# I2C2_6_0.net
KiCad netlist of a schematic drawn in EAGLE
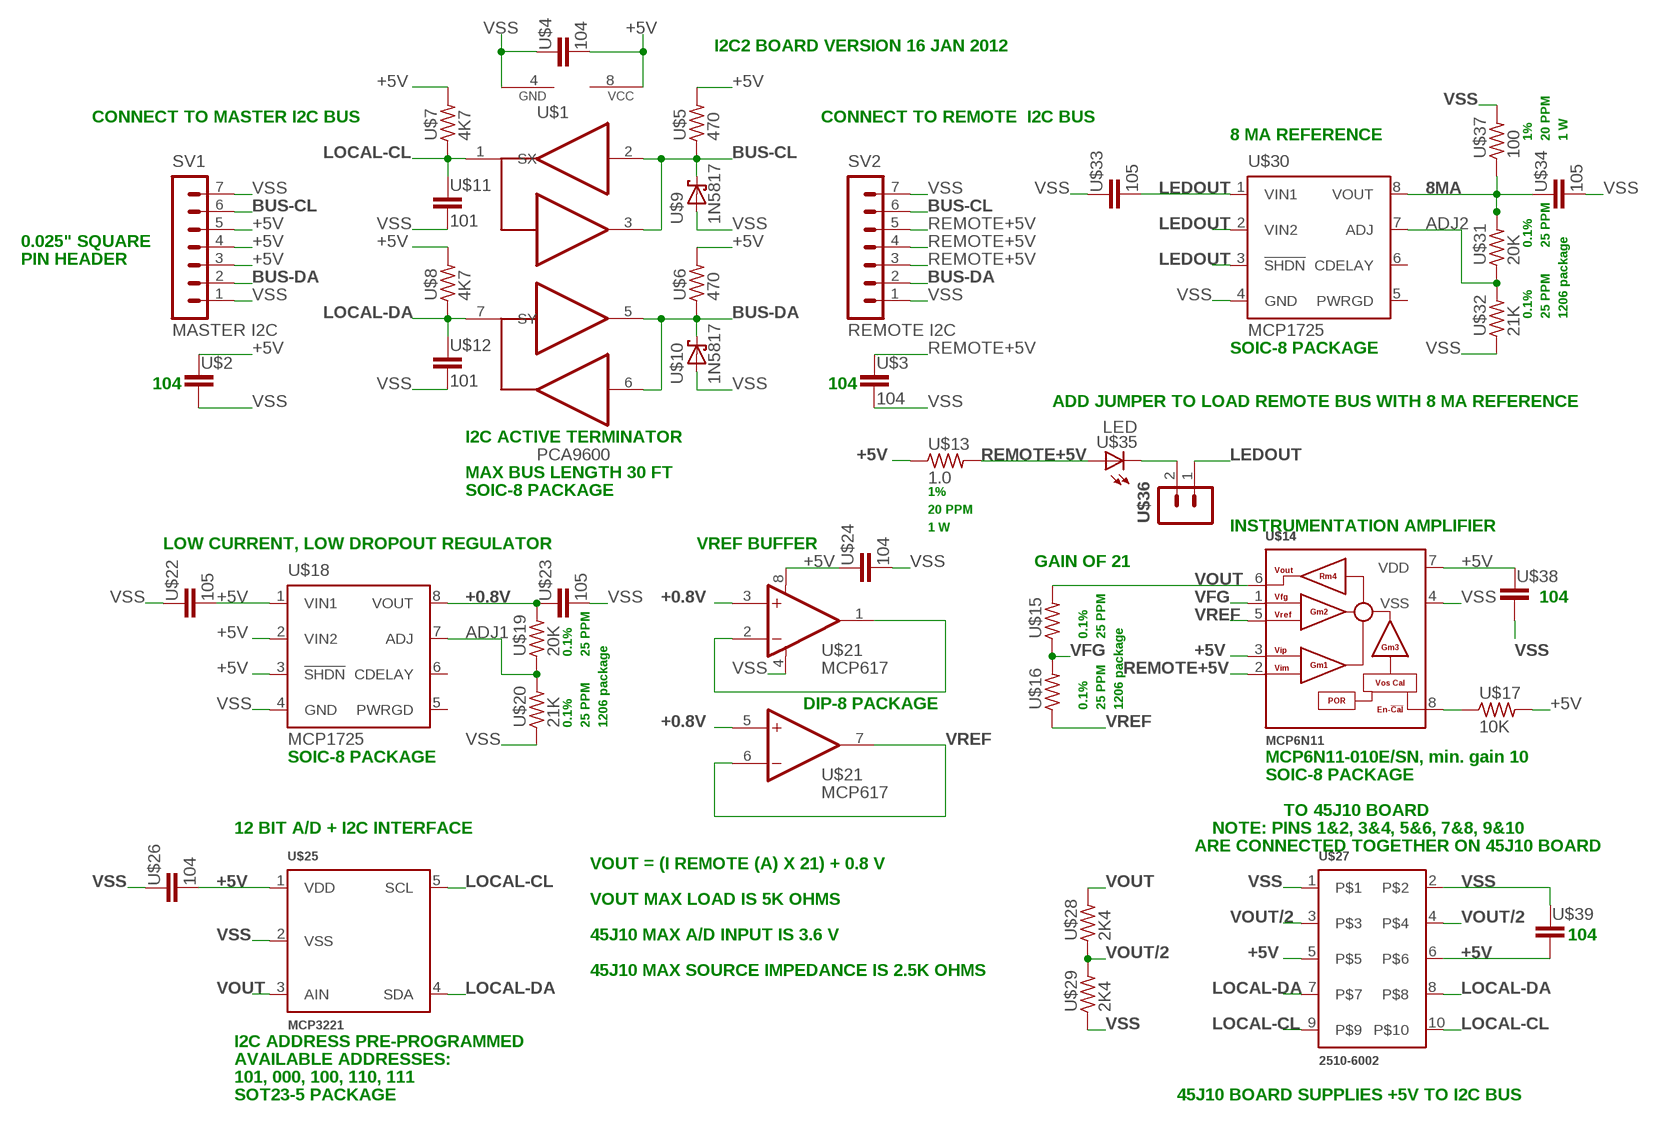
[diagram p0: schematic, sheet 1]

(export (version "E")
  (design (tool "Eeschema 10.0.6"))
  (components
    (comp (ref "SV1")
      (value "MASTER I2C")
      (footprint "eagle-import:MA07-1")
      (libsource (lib "eagle-import") (part "MA07-1"))
    )
    (comp (ref "SV2")
      (value "REMOTE I2C")
      (footprint "eagle-import:MA07-1")
      (libsource (lib "eagle-import") (part "MA07-1"))
    )
    (comp (ref "U$1")
      (value "PCA9600")
      (footprint "eagle-import:SO08")
      (libsource (lib "eagle-import") (part "PCA9600SO8"))
    )
    (comp (ref "U$2")
      (value "C2.5-5")
      (footprint "eagle-import:C2.5-5")
      (libsource (lib "eagle-import") (part "C2.5-5"))
    )
    (comp (ref "U$3")
      (value "104")
      (footprint "eagle-import:C2.5-5")
      (libsource (lib "eagle-import") (part "C2.5-5"))
    )
    (comp (ref "U$4")
      (value "104")
      (footprint "eagle-import:C2.5-5")
      (libsource (lib "eagle-import") (part "C2.5-5"))
    )
    (comp (ref "U$5")
      (value "470")
      (footprint "eagle-import:R-1_4W")
      (libsource (lib "eagle-import") (part "R-1/4W"))
    )
    (comp (ref "U$6")
      (value "470")
      (footprint "eagle-import:R-1_4W")
      (libsource (lib "eagle-import") (part "R-1/4W"))
    )
    (comp (ref "U$7")
      (value "4K7")
      (footprint "eagle-import:R-1_4W")
      (libsource (lib "eagle-import") (part "R-1/4W"))
    )
    (comp (ref "U$8")
      (value "4K7")
      (footprint "eagle-import:R-1_4W")
      (libsource (lib "eagle-import") (part "R-1/4W"))
    )
    (comp (ref "U$9")
      (value "1N5817")
      (footprint "eagle-import:1N5817")
      (libsource (lib "eagle-import") (part "1N5817P"))
    )
    (comp (ref "U$10")
      (value "1N5817")
      (footprint "eagle-import:1N5817")
      (libsource (lib "eagle-import") (part "1N5817P"))
    )
    (comp (ref "U$11")
      (value "101")
      (footprint "eagle-import:C2.5-5")
      (libsource (lib "eagle-import") (part "C2.5-5"))
    )
    (comp (ref "U$12")
      (value "101")
      (footprint "eagle-import:C2.5-5")
      (libsource (lib "eagle-import") (part "C2.5-5"))
    )
    (comp (ref "U$13")
      (value "1.0")
      (footprint "eagle-import:R-1W")
      (libsource (lib "eagle-import") (part "R-1W-20PPM"))
    )
    (comp (ref "U$14")
      (value "MCP6N11")
      (footprint "eagle-import:SO08")
      (libsource (lib "eagle-import") (part "MCP6N11-SO08"))
    )
    (comp (ref "U$15")
      (value "R1206")
      (footprint "eagle-import:R1206")
      (libsource (lib "eagle-import") (part "R1206"))
    )
    (comp (ref "U$16")
      (value "R1206")
      (footprint "eagle-import:R1206")
      (libsource (lib "eagle-import") (part "R1206"))
    )
    (comp (ref "U$17")
      (value "10K")
      (footprint "eagle-import:R-1_4W")
      (libsource (lib "eagle-import") (part "R-1/4W"))
    )
    (comp (ref "U$18")
      (value "MCP1725")
      (footprint "eagle-import:SO08")
      (libsource (lib "eagle-import") (part "MCP1725-ADJ"))
    )
    (comp (ref "U$19")
      (value "20K")
      (footprint "eagle-import:R1206")
      (libsource (lib "eagle-import") (part "R1206"))
    )
    (comp (ref "U$20")
      (value "21K")
      (footprint "eagle-import:R1206")
      (libsource (lib "eagle-import") (part "R1206"))
    )
    (comp (ref "U$21")
      (value "MCP617")
      (footprint "eagle-import:DIL08")
      (libsource (lib "eagle-import") (part "MCP617-I/P"))
    )
    (comp (ref "U$22")
      (value "105")
      (footprint "eagle-import:C2.5-5")
      (libsource (lib "eagle-import") (part "C2.5-5"))
    )
    (comp (ref "U$23")
      (value "105")
      (footprint "eagle-import:C2.5-5")
      (libsource (lib "eagle-import") (part "C2.5-5"))
    )
    (comp (ref "U$24")
      (value "104")
      (footprint "eagle-import:C2.5-5")
      (libsource (lib "eagle-import") (part "C2.5-5"))
    )
    (comp (ref "U$25")
      (value "MCP3221")
      (footprint "eagle-import:SOT23-5")
      (libsource (lib "eagle-import") (part "MCP3221"))
    )
    (comp (ref "U$26")
      (value "104")
      (footprint "eagle-import:C2.5-5")
      (libsource (lib "eagle-import") (part "C2.5-5"))
    )
    (comp (ref "U$27")
      (value "2510-6002")
      (footprint "eagle-import:2510-6002")
      (libsource (lib "eagle-import") (part "2510-6002"))
    )
    (comp (ref "U$28")
      (value "2K4")
      (footprint "eagle-import:R-1_4W")
      (libsource (lib "eagle-import") (part "R-1/4W"))
    )
    (comp (ref "U$29")
      (value "2K4")
      (footprint "eagle-import:R-1_4W")
      (libsource (lib "eagle-import") (part "R-1/4W"))
    )
    (comp (ref "U$30")
      (value "MCP1725")
      (footprint "eagle-import:SO08")
      (libsource (lib "eagle-import") (part "MCP1725-ADJ"))
    )
    (comp (ref "U$31")
      (value "20K")
      (footprint "eagle-import:R1206")
      (libsource (lib "eagle-import") (part "R1206"))
    )
    (comp (ref "U$32")
      (value "21K")
      (footprint "eagle-import:R1206")
      (libsource (lib "eagle-import") (part "R1206"))
    )
    (comp (ref "U$33")
      (value "105")
      (footprint "eagle-import:C2.5-5")
      (libsource (lib "eagle-import") (part "C2.5-5"))
    )
    (comp (ref "U$34")
      (value "105")
      (footprint "eagle-import:C2.5-5")
      (libsource (lib "eagle-import") (part "C2.5-5"))
    )
    (comp (ref "U$35")
      (value "LED")
      (footprint "eagle-import:LED1206")
      (libsource (lib "eagle-import") (part "LED-SMD-1206"))
    )
    (comp (ref "U$36")
      (value "MA02-1")
      (footprint "eagle-import:MA02-1")
      (libsource (lib "eagle-import") (part "MA02-1"))
    )
    (comp (ref "U$37")
      (value "100")
      (footprint "eagle-import:R-1W")
      (libsource (lib "eagle-import") (part "R-1W-20PPM"))
    )
    (comp (ref "U$38")
      (value "C2.5-5")
      (footprint "eagle-import:C2.5-5")
      (libsource (lib "eagle-import") (part "C2.5-5"))
    )
    (comp (ref "U$39")
      (value "C2.5-5")
      (footprint "eagle-import:C2.5-5")
      (libsource (lib "eagle-import") (part "C2.5-5"))
    )
  )
  (nets
    (net (code "1") (name "/+0.8V") (class "Default")
      (node (ref "U$18") (pin "8") (pinfunction "VOUT_8") (pintype "power_in"))
      (node (ref "U$19") (pin "2") (pinfunction "2_2") (pintype "passive"))
      (node (ref "U$21") (pin "3") (pinfunction "+IN_3") (pintype "input"))
      (node (ref "U$21") (pin "5") (pinfunction "+IN1_5") (pintype "input"))
      (node (ref "U$23") (pin "1") (pinfunction "1_1") (pintype "passive"))
    )
    (net (code "2") (name "/+5V") (class "Default")
      (node (ref "SV1") (pin "3") (pinfunction "3_3") (pintype "passive"))
      (node (ref "SV1") (pin "4") (pinfunction "4_4") (pintype "passive"))
      (node (ref "SV1") (pin "5") (pinfunction "5_5") (pintype "passive"))
      (node (ref "U$1") (pin "8") (pinfunction "VCC_8") (pintype "power_in"))
      (node (ref "U$13") (pin "1") (pinfunction "1_1") (pintype "passive"))
      (node (ref "U$14") (pin "3") (pinfunction "VIP_3") (pintype "input"))
      (node (ref "U$14") (pin "7") (pinfunction "VDD_7") (pintype "power_in"))
      (node (ref "U$17") (pin "2") (pinfunction "2_2") (pintype "passive"))
      (node (ref "U$18") (pin "1") (pinfunction "VIN1_1") (pintype "power_in"))
      (node (ref "U$18") (pin "2") (pinfunction "VIN2_2") (pintype "power_in"))
      (node (ref "U$18") (pin "3") (pinfunction "~{SHDN}_3") (pintype "input"))
      (node (ref "U$2") (pin "1") (pinfunction "1_1") (pintype "passive"))
      (node (ref "U$21") (pin "8") (pinfunction "V+_8") (pintype "power_in"))
      (node (ref "U$22") (pin "2") (pinfunction "2_2") (pintype "passive"))
      (node (ref "U$24") (pin "1") (pinfunction "1_1") (pintype "passive"))
      (node (ref "U$25") (pin "1") (pinfunction "VDD_1") (pintype "power_in"))
      (node (ref "U$26") (pin "2") (pinfunction "2_2") (pintype "passive"))
      (node (ref "U$27") (pin "5") (pinfunction "P$5_5") (pintype "passive"))
      (node (ref "U$27") (pin "6") (pinfunction "P$6_6") (pintype "passive"))
      (node (ref "U$38") (pin "1") (pinfunction "1_1") (pintype "passive"))
      (node (ref "U$39") (pin "2") (pinfunction "2_2") (pintype "passive"))
      (node (ref "U$4") (pin "2") (pinfunction "2_2") (pintype "passive"))
      (node (ref "U$5") (pin "2") (pinfunction "2_2") (pintype "passive"))
      (node (ref "U$6") (pin "2") (pinfunction "2_2") (pintype "passive"))
      (node (ref "U$7") (pin "2") (pinfunction "2_2") (pintype "passive"))
      (node (ref "U$8") (pin "2") (pinfunction "2_2") (pintype "passive"))
    )
    (net (code "3") (name "/8MA") (class "Default")
      (node (ref "U$30") (pin "8") (pinfunction "VOUT_8") (pintype "power_in"))
      (node (ref "U$31") (pin "2") (pinfunction "2_2") (pintype "passive"))
      (node (ref "U$34") (pin "1") (pinfunction "1_1") (pintype "passive"))
      (node (ref "U$37") (pin "1") (pinfunction "1_1") (pintype "passive"))
    )
    (net (code "4") (name "/ADJ1") (class "Default")
      (node (ref "U$18") (pin "7") (pinfunction "ADJ_7") (pintype "input"))
      (node (ref "U$19") (pin "1") (pinfunction "1_1") (pintype "passive"))
      (node (ref "U$20") (pin "2") (pinfunction "2_2") (pintype "passive"))
    )
    (net (code "5") (name "/ADJ2") (class "Default")
      (node (ref "U$30") (pin "7") (pinfunction "ADJ_7") (pintype "input"))
      (node (ref "U$31") (pin "1") (pinfunction "1_1") (pintype "passive"))
      (node (ref "U$32") (pin "2") (pinfunction "2_2") (pintype "passive"))
    )
    (net (code "6") (name "/BUS-CL") (class "Default")
      (node (ref "SV1") (pin "6") (pinfunction "6_6") (pintype "passive"))
      (node (ref "SV2") (pin "6") (pinfunction "6_6") (pintype "passive"))
      (node (ref "U$1") (pin "2") (pinfunction "RX_2") (pintype "input"))
      (node (ref "U$1") (pin "3") (pinfunction "TX_3") (pintype "output"))
      (node (ref "U$5") (pin "1") (pinfunction "1_1") (pintype "passive"))
      (node (ref "U$9") (pin "C") (pinfunction "C_C") (pintype "passive"))
    )
    (net (code "7") (name "/BUS-DA") (class "Default")
      (node (ref "SV1") (pin "2") (pinfunction "2_2") (pintype "passive"))
      (node (ref "SV2") (pin "2") (pinfunction "2_2") (pintype "passive"))
      (node (ref "U$1") (pin "5") (pinfunction "TY_5") (pintype "output"))
      (node (ref "U$1") (pin "6") (pinfunction "RY_6") (pintype "input"))
      (node (ref "U$10") (pin "C") (pinfunction "C_C") (pintype "passive"))
      (node (ref "U$6") (pin "1") (pinfunction "1_1") (pintype "passive"))
    )
    (net (code "8") (name "/LEDOUT") (class "Default")
      (node (ref "U$30") (pin "1") (pinfunction "VIN1_1") (pintype "power_in"))
      (node (ref "U$30") (pin "2") (pinfunction "VIN2_2") (pintype "power_in"))
      (node (ref "U$30") (pin "3") (pinfunction "~{SHDN}_3") (pintype "input"))
      (node (ref "U$33") (pin "2") (pinfunction "2_2") (pintype "passive"))
      (node (ref "U$36") (pin "1") (pinfunction "1_1") (pintype "passive"))
    )
    (net (code "9") (name "/LOCAL-CL") (class "Default")
      (node (ref "U$1") (pin "1") (pinfunction "SX_1") (pintype "bidirectional"))
      (node (ref "U$11") (pin "1") (pinfunction "1_1") (pintype "passive"))
      (node (ref "U$25") (pin "5") (pinfunction "SCL_5") (pintype "bidirectional"))
      (node (ref "U$27") (pin "10") (pinfunction "P$10_10") (pintype "passive"))
      (node (ref "U$27") (pin "9") (pinfunction "P$9_9") (pintype "passive"))
      (node (ref "U$7") (pin "1") (pinfunction "1_1") (pintype "passive"))
    )
    (net (code "10") (name "/LOCAL-DA") (class "Default")
      (node (ref "U$1") (pin "7") (pinfunction "SY_7") (pintype "bidirectional"))
      (node (ref "U$12") (pin "1") (pinfunction "1_1") (pintype "passive"))
      (node (ref "U$25") (pin "4") (pinfunction "SDA_4") (pintype "bidirectional"))
      (node (ref "U$27") (pin "7") (pinfunction "P$7_7") (pintype "passive"))
      (node (ref "U$27") (pin "8") (pinfunction "P$8_8") (pintype "passive"))
      (node (ref "U$8") (pin "1") (pinfunction "1_1") (pintype "passive"))
    )
    (net (code "11") (name "/REMOTE+5V") (class "Default")
      (node (ref "SV2") (pin "3") (pinfunction "3_3") (pintype "passive"))
      (node (ref "SV2") (pin "4") (pinfunction "4_4") (pintype "passive"))
      (node (ref "SV2") (pin "5") (pinfunction "5_5") (pintype "passive"))
      (node (ref "U$13") (pin "2") (pinfunction "2_2") (pintype "passive"))
      (node (ref "U$14") (pin "2") (pinfunction "VIM_2") (pintype "input"))
      (node (ref "U$3") (pin "1") (pinfunction "1_1") (pintype "passive"))
      (node (ref "U$35") (pin "A") (pinfunction "A_A") (pintype "passive"))
    )
    (net (code "12") (name "/VFG") (class "Default")
      (node (ref "U$14") (pin "1") (pinfunction "VFG_1") (pintype "input"))
      (node (ref "U$15") (pin "1") (pinfunction "1_1") (pintype "passive"))
      (node (ref "U$16") (pin "2") (pinfunction "2_2") (pintype "passive"))
    )
    (net (code "13") (name "/VOUT") (class "Default")
      (node (ref "U$14") (pin "6") (pinfunction "VOUT_6") (pintype "output"))
      (node (ref "U$15") (pin "2") (pinfunction "2_2") (pintype "passive"))
      (node (ref "U$25") (pin "3") (pinfunction "AIN_3") (pintype "input"))
      (node (ref "U$28") (pin "2") (pinfunction "2_2") (pintype "passive"))
    )
    (net (code "14") (name "/VOUT{slash}2") (class "Default")
      (node (ref "U$27") (pin "3") (pinfunction "P$3_3") (pintype "passive"))
      (node (ref "U$27") (pin "4") (pinfunction "P$4_4") (pintype "passive"))
      (node (ref "U$28") (pin "1") (pinfunction "1_1") (pintype "passive"))
      (node (ref "U$29") (pin "2") (pinfunction "2_2") (pintype "passive"))
    )
    (net (code "15") (name "/VREF") (class "Default")
      (node (ref "U$14") (pin "5") (pinfunction "VREF_5") (pintype "input"))
      (node (ref "U$16") (pin "1") (pinfunction "1_1") (pintype "passive"))
      (node (ref "U$21") (pin "6") (pinfunction "-IN1_6") (pintype "input"))
      (node (ref "U$21") (pin "7") (pinfunction "OUT1_7") (pintype "output"))
    )
    (net (code "16") (name "/VSS") (class "Default")
      (node (ref "SV1") (pin "1") (pinfunction "1_1") (pintype "passive"))
      (node (ref "SV1") (pin "7") (pinfunction "7_7") (pintype "passive"))
      (node (ref "SV2") (pin "1") (pinfunction "1_1") (pintype "passive"))
      (node (ref "SV2") (pin "7") (pinfunction "7_7") (pintype "passive"))
      (node (ref "U$1") (pin "4") (pinfunction "GND_4") (pintype "power_in"))
      (node (ref "U$10") (pin "A") (pinfunction "A_A") (pintype "passive"))
      (node (ref "U$11") (pin "2") (pinfunction "2_2") (pintype "passive"))
      (node (ref "U$12") (pin "2") (pinfunction "2_2") (pintype "passive"))
      (node (ref "U$14") (pin "4") (pinfunction "VSS_4") (pintype "power_in"))
      (node (ref "U$18") (pin "4") (pinfunction "GND_4") (pintype "power_in"))
      (node (ref "U$2") (pin "2") (pinfunction "2_2") (pintype "passive"))
      (node (ref "U$20") (pin "1") (pinfunction "1_1") (pintype "passive"))
      (node (ref "U$21") (pin "4") (pinfunction "V-_4") (pintype "power_in"))
      (node (ref "U$22") (pin "1") (pinfunction "1_1") (pintype "passive"))
      (node (ref "U$23") (pin "2") (pinfunction "2_2") (pintype "passive"))
      (node (ref "U$24") (pin "2") (pinfunction "2_2") (pintype "passive"))
      (node (ref "U$25") (pin "2") (pinfunction "VSS_2") (pintype "power_in"))
      (node (ref "U$26") (pin "1") (pinfunction "1_1") (pintype "passive"))
      (node (ref "U$27") (pin "1") (pinfunction "P$1_1") (pintype "passive"))
      (node (ref "U$27") (pin "2") (pinfunction "P$2_2") (pintype "passive"))
      (node (ref "U$29") (pin "1") (pinfunction "1_1") (pintype "passive"))
      (node (ref "U$3") (pin "2") (pinfunction "2_2") (pintype "passive"))
      (node (ref "U$30") (pin "4") (pinfunction "GND_4") (pintype "power_in"))
      (node (ref "U$32") (pin "1") (pinfunction "1_1") (pintype "passive"))
      (node (ref "U$33") (pin "1") (pinfunction "1_1") (pintype "passive"))
      (node (ref "U$34") (pin "2") (pinfunction "2_2") (pintype "passive"))
      (node (ref "U$37") (pin "2") (pinfunction "2_2") (pintype "passive"))
      (node (ref "U$38") (pin "2") (pinfunction "2_2") (pintype "passive"))
      (node (ref "U$39") (pin "1") (pinfunction "1_1") (pintype "passive"))
      (node (ref "U$4") (pin "1") (pinfunction "1_1") (pintype "passive"))
      (node (ref "U$9") (pin "A") (pinfunction "A_A") (pintype "passive"))
    )
    (net (code "17") (name "Net-(U$14-EN)") (class "Default")
      (node (ref "U$14") (pin "8") (pinfunction "EN_8") (pintype "input"))
      (node (ref "U$17") (pin "1") (pinfunction "1_1") (pintype "passive"))
    )
    (net (code "18") (name "Net-(U$21--IN)") (class "Default")
      (node (ref "U$21") (pin "1") (pinfunction "OUT_1") (pintype "output"))
      (node (ref "U$21") (pin "2") (pinfunction "-IN_2") (pintype "input"))
    )
    (net (code "19") (name "Net-(U$35-PadC)") (class "Default")
      (node (ref "U$35") (pin "C") (pinfunction "C_C") (pintype "passive"))
      (node (ref "U$36") (pin "2") (pinfunction "2_2") (pintype "passive"))
    )
    (net (code "20") (name "unconnected-(U$18-CDELAY-Pad6)") (class "Default")
      (node (ref "U$18") (pin "6") (pinfunction "CDELAY_6") (pintype "input"))
    )
    (net (code "21") (name "unconnected-(U$18-PWRGD-Pad5)") (class "Default")
      (node (ref "U$18") (pin "5") (pinfunction "PWRGD_5") (pintype "output"))
    )
    (net (code "22") (name "unconnected-(U$30-CDELAY-Pad6)") (class "Default")
      (node (ref "U$30") (pin "6") (pinfunction "CDELAY_6") (pintype "input"))
    )
    (net (code "23") (name "unconnected-(U$30-PWRGD-Pad5)") (class "Default")
      (node (ref "U$30") (pin "5") (pinfunction "PWRGD_5") (pintype "output"))
    )
  )
)
